# vacmonitor.net
KiCad netlist of a schematic drawn in EAGLE
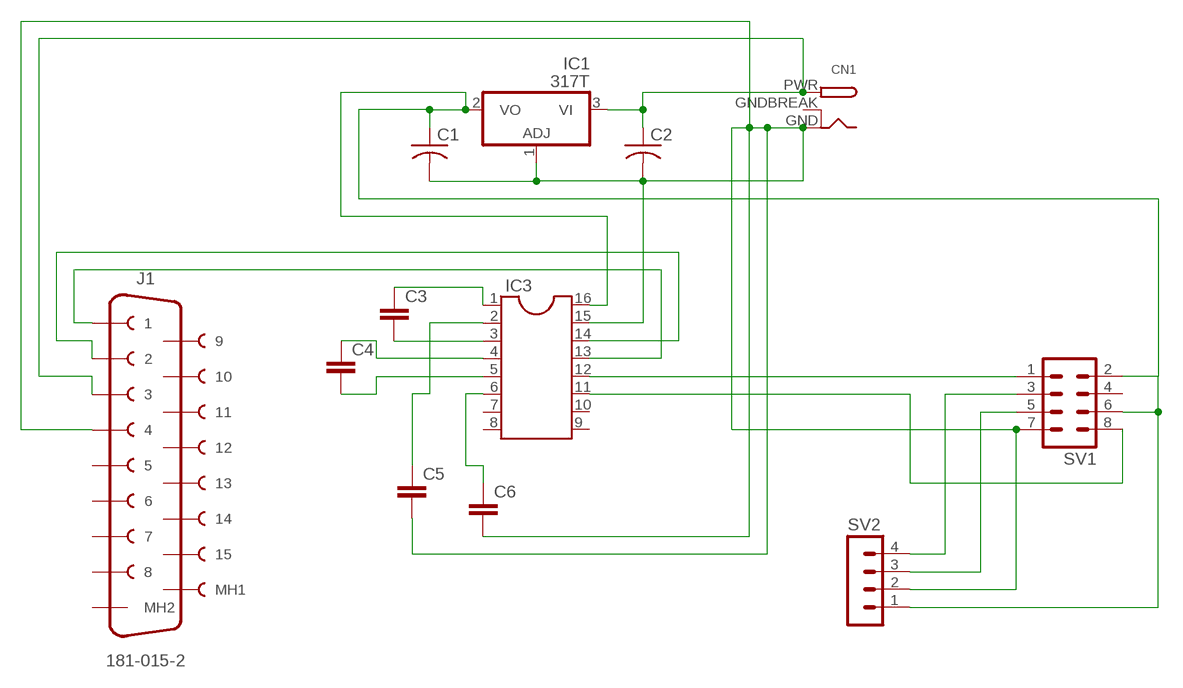
[diagram p0: schematic, sheet 1]

(export (version "E")
  (design (tool "Eeschema 10.0.6"))
  (components
    (comp (ref "C1")
      (value "C-US025-024X044")
      (footprint "eagle-import:C025-024X044")
      (libsource (lib "eagle-import") (part "C-US025-024X044"))
    )
    (comp (ref "C2")
      (value "C-US025-024X044")
      (footprint "eagle-import:C025-024X044")
      (libsource (lib "eagle-import") (part "C-US025-024X044"))
    )
    (comp (ref "C3")
      (value "C5/3")
      (footprint "eagle-import:C5B3")
      (libsource (lib "eagle-import") (part "C5/3"))
    )
    (comp (ref "C4")
      (value "C5/3")
      (footprint "eagle-import:C5B3")
      (libsource (lib "eagle-import") (part "C5/3"))
    )
    (comp (ref "C5")
      (value "C5/3")
      (footprint "eagle-import:C5B3")
      (libsource (lib "eagle-import") (part "C5/3"))
    )
    (comp (ref "C6")
      (value "C5/3")
      (footprint "eagle-import:C5B3")
      (libsource (lib "eagle-import") (part "C5/3"))
    )
    (comp (ref "CN1")
      (value "DCBARRELPTH")
      (footprint "eagle-import:DCJACK_2MM_PTH")
      (libsource (lib "eagle-import") (part "DCBARRELPTH"))
    )
    (comp (ref "IC1")
      (value "317T")
      (footprint "eagle-import:TO220H")
      (libsource (lib "eagle-import") (part "317T"))
    )
    (comp (ref "IC3")
      (value "DIL16")
      (footprint "eagle-import:DIL16")
      (libsource (lib "eagle-import") (part "DIL16"))
    )
    (comp (ref "J1")
      (value "181-015-2")
      (footprint "eagle-import:181-015-213R561")
      (fields (field (name "MANUFACTURER") "NorComp") (field (name "MPN") "181-015-213R561"))
      (libsource (lib "eagle-import") (part "181-015-2"))
    )
    (comp (ref "SV1")
      (value "MA04-2")
      (footprint "eagle-import:MA04-2")
      (libsource (lib "eagle-import") (part "MA04-2"))
    )
    (comp (ref "SV2")
      (value "MA04-1")
      (footprint "eagle-import:MA04-1")
      (libsource (lib "eagle-import") (part "MA04-1"))
    )
  )
  (nets
    (net (code "1") (name "/GNDBREAK") (class "Default")
      (node (ref "CN1") (pin "GNDBREAK") (pinfunction "GNDBREAK_GNDBREAK") (pintype "power_in"))
    )
    (net (code "2") (name "/MH1") (class "Default")
      (node (ref "J1") (pin "MH1") (pinfunction "MH1_MH1") (pintype "power_in"))
    )
    (net (code "3") (name "/MH2") (class "Default")
      (node (ref "J1") (pin "MH2") (pinfunction "MH2_MH2") (pintype "power_in"))
    )
    (net (code "4") (name "Net-(C3-Pad1)") (class "Default")
      (node (ref "C3") (pin "1") (pinfunction "1_1") (pintype "passive"))
      (node (ref "IC3") (pin "1") (pinfunction "1_1") (pintype "passive"))
    )
    (net (code "5") (name "Net-(C3-Pad2)") (class "Default")
      (node (ref "C3") (pin "2") (pinfunction "2_2") (pintype "passive"))
      (node (ref "IC3") (pin "3") (pinfunction "3_3") (pintype "passive"))
    )
    (net (code "6") (name "Net-(C4-Pad1)") (class "Default")
      (node (ref "C4") (pin "1") (pinfunction "1_1") (pintype "passive"))
      (node (ref "IC3") (pin "4") (pinfunction "4_4") (pintype "passive"))
    )
    (net (code "7") (name "Net-(C4-Pad2)") (class "Default")
      (node (ref "C4") (pin "2") (pinfunction "2_2") (pintype "passive"))
      (node (ref "IC3") (pin "5") (pinfunction "5_5") (pintype "passive"))
    )
    (net (code "8") (name "Net-(C5-Pad1)") (class "Default")
      (node (ref "C5") (pin "1") (pinfunction "1_1") (pintype "passive"))
      (node (ref "IC3") (pin "2") (pinfunction "2_2") (pintype "passive"))
    )
    (net (code "9") (name "Net-(C6-Pad1)") (class "Default")
      (node (ref "C6") (pin "1") (pinfunction "1_1") (pintype "passive"))
      (node (ref "IC3") (pin "6") (pinfunction "6_6") (pintype "passive"))
    )
    (net (code "10") (name "Net-(IC1-ADJ)") (class "Default")
      (node (ref "C1") (pin "2") (pinfunction "2_2") (pintype "passive"))
      (node (ref "C2") (pin "2") (pinfunction "2_2") (pintype "passive"))
      (node (ref "C5") (pin "2") (pinfunction "2_2") (pintype "passive"))
      (node (ref "C6") (pin "2") (pinfunction "2_2") (pintype "passive"))
      (node (ref "CN1") (pin "GND") (pinfunction "GND_GND") (pintype "power_in"))
      (node (ref "IC1") (pin "1") (pinfunction "ADJ_1") (pintype "input"))
      (node (ref "IC3") (pin "15") (pinfunction "15_15") (pintype "passive"))
      (node (ref "J1") (pin "4") (pinfunction "4_4") (pintype "passive"))
      (node (ref "SV1") (pin "7") (pinfunction "7_7") (pintype "passive"))
      (node (ref "SV2") (pin "2") (pinfunction "2_2") (pintype "passive"))
    )
    (net (code "11") (name "Net-(IC1-VI)") (class "Default")
      (node (ref "C2") (pin "1") (pinfunction "1_1") (pintype "passive"))
      (node (ref "CN1") (pin "PWR") (pinfunction "PWR_PWR") (pintype "power_in"))
      (node (ref "IC1") (pin "3") (pinfunction "VI_3") (pintype "input"))
      (node (ref "J1") (pin "3") (pinfunction "3_3") (pintype "passive"))
    )
    (net (code "12") (name "Net-(IC1-VO)") (class "Default")
      (node (ref "C1") (pin "1") (pinfunction "1_1") (pintype "passive"))
      (node (ref "IC1") (pin "2") (pinfunction "VO_2") (pintype "passive"))
      (node (ref "IC3") (pin "16") (pinfunction "16_16") (pintype "passive"))
      (node (ref "SV1") (pin "2") (pinfunction "2_2") (pintype "passive"))
      (node (ref "SV1") (pin "6") (pinfunction "6_6") (pintype "passive"))
      (node (ref "SV2") (pin "1") (pinfunction "1_1") (pintype "passive"))
    )
    (net (code "13") (name "Net-(IC3-Pad11)") (class "Default")
      (node (ref "IC3") (pin "11") (pinfunction "11_11") (pintype "passive"))
      (node (ref "SV1") (pin "8") (pinfunction "8_8") (pintype "passive"))
    )
    (net (code "14") (name "Net-(IC3-Pad12)") (class "Default")
      (node (ref "IC3") (pin "12") (pinfunction "12_12") (pintype "passive"))
      (node (ref "SV1") (pin "1") (pinfunction "1_1") (pintype "passive"))
    )
    (net (code "15") (name "Net-(IC3-Pad13)") (class "Default")
      (node (ref "IC3") (pin "13") (pinfunction "13_13") (pintype "passive"))
      (node (ref "J1") (pin "1") (pinfunction "1_1") (pintype "passive"))
    )
    (net (code "16") (name "Net-(IC3-Pad14)") (class "Default")
      (node (ref "IC3") (pin "14") (pinfunction "14_14") (pintype "passive"))
      (node (ref "J1") (pin "2") (pinfunction "2_2") (pintype "passive"))
    )
    (net (code "17") (name "Net-(SV1-Pad3)") (class "Default")
      (node (ref "SV1") (pin "3") (pinfunction "3_3") (pintype "passive"))
      (node (ref "SV2") (pin "4") (pinfunction "4_4") (pintype "passive"))
    )
    (net (code "18") (name "Net-(SV1-Pad5)") (class "Default")
      (node (ref "SV1") (pin "5") (pinfunction "5_5") (pintype "passive"))
      (node (ref "SV2") (pin "3") (pinfunction "3_3") (pintype "passive"))
    )
    (net (code "19") (name "unconnected-(IC3-Pad7)") (class "Default")
      (node (ref "IC3") (pin "7") (pinfunction "7_7") (pintype "passive"))
    )
    (net (code "20") (name "unconnected-(IC3-Pad8)") (class "Default")
      (node (ref "IC3") (pin "8") (pinfunction "8_8") (pintype "passive"))
    )
    (net (code "21") (name "unconnected-(IC3-Pad9)") (class "Default")
      (node (ref "IC3") (pin "9") (pinfunction "9_9") (pintype "passive"))
    )
    (net (code "22") (name "unconnected-(IC3-Pad10)") (class "Default")
      (node (ref "IC3") (pin "10") (pinfunction "10_10") (pintype "passive"))
    )
    (net (code "23") (name "unconnected-(J1-Pad5)") (class "Default")
      (node (ref "J1") (pin "5") (pinfunction "5_5") (pintype "passive"))
    )
    (net (code "24") (name "unconnected-(J1-Pad6)") (class "Default")
      (node (ref "J1") (pin "6") (pinfunction "6_6") (pintype "passive"))
    )
    (net (code "25") (name "unconnected-(J1-Pad7)") (class "Default")
      (node (ref "J1") (pin "7") (pinfunction "7_7") (pintype "passive"))
    )
    (net (code "26") (name "unconnected-(J1-Pad8)") (class "Default")
      (node (ref "J1") (pin "8") (pinfunction "8_8") (pintype "passive"))
    )
    (net (code "27") (name "unconnected-(J1-Pad9)") (class "Default")
      (node (ref "J1") (pin "9") (pinfunction "9_9") (pintype "passive"))
    )
    (net (code "28") (name "unconnected-(J1-Pad10)") (class "Default")
      (node (ref "J1") (pin "10") (pinfunction "10_10") (pintype "passive"))
    )
    (net (code "29") (name "unconnected-(J1-Pad11)") (class "Default")
      (node (ref "J1") (pin "11") (pinfunction "11_11") (pintype "passive"))
    )
    (net (code "30") (name "unconnected-(J1-Pad12)") (class "Default")
      (node (ref "J1") (pin "12") (pinfunction "12_12") (pintype "passive"))
    )
    (net (code "31") (name "unconnected-(J1-Pad13)") (class "Default")
      (node (ref "J1") (pin "13") (pinfunction "13_13") (pintype "passive"))
    )
    (net (code "32") (name "unconnected-(J1-Pad14)") (class "Default")
      (node (ref "J1") (pin "14") (pinfunction "14_14") (pintype "passive"))
    )
    (net (code "33") (name "unconnected-(J1-Pad15)") (class "Default")
      (node (ref "J1") (pin "15") (pinfunction "15_15") (pintype "passive"))
    )
    (net (code "34") (name "unconnected-(SV1-Pad4)") (class "Default")
      (node (ref "SV1") (pin "4") (pinfunction "4_4") (pintype "passive"))
    )
  )
)
